# control_board.net
KiCad netlist of a schematic drawn in EAGLE
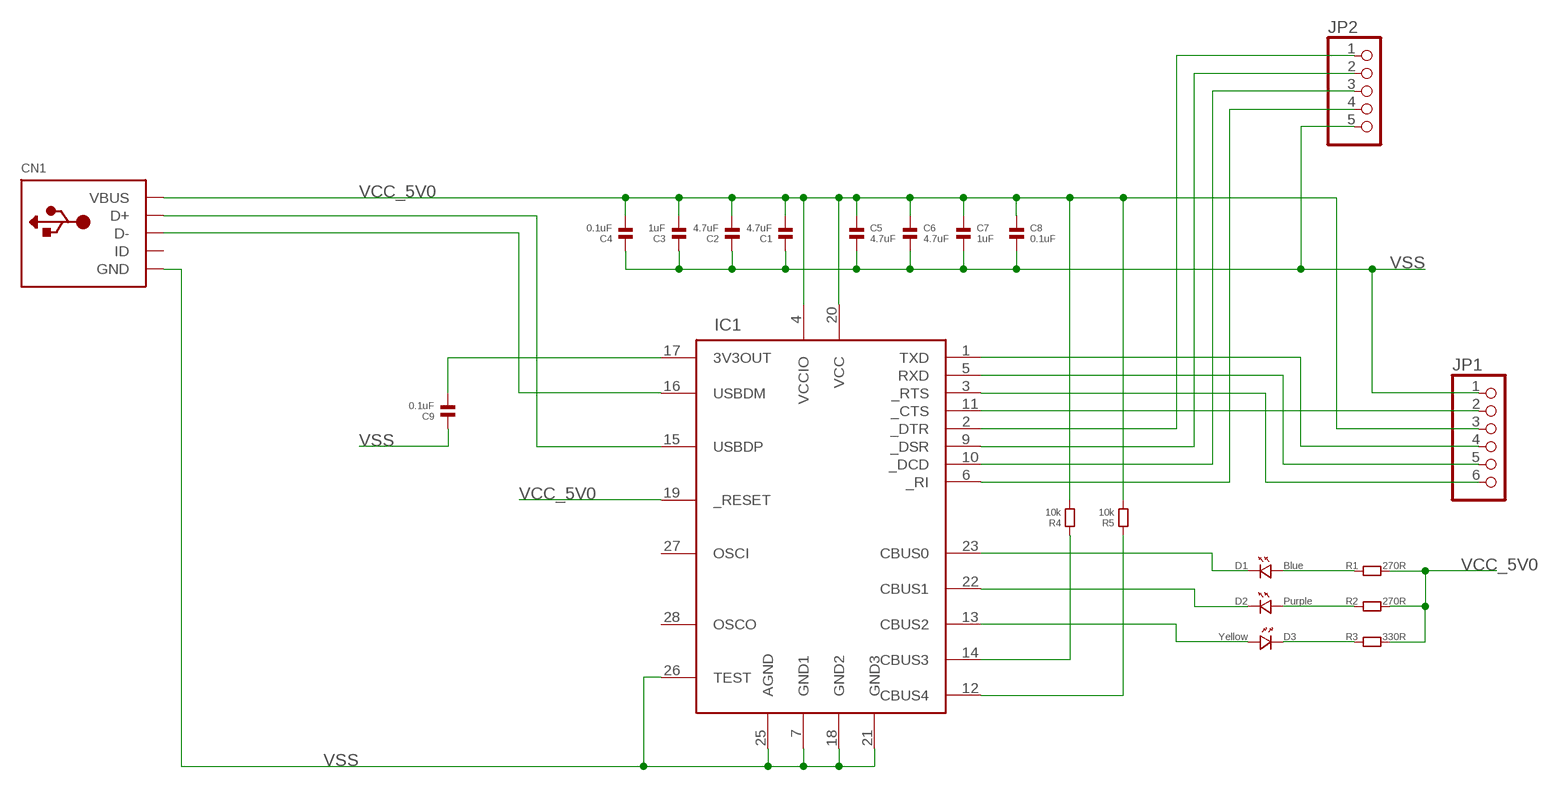
[diagram p0: schematic, sheet 1]

(export (version "E")
  (design (tool "Eeschema 10.0.6"))
  (components
    (comp (ref "C1")
      (value "4.7uF")
      (footprint "eagle-import:0603")
      (libsource (lib "eagle-import") (part "CAPACITOR.0603"))
    )
    (comp (ref "C2")
      (value "4.7uF")
      (footprint "eagle-import:0603")
      (libsource (lib "eagle-import") (part "CAPACITOR.0603"))
    )
    (comp (ref "C3")
      (value "1uF")
      (footprint "eagle-import:0603")
      (libsource (lib "eagle-import") (part "CAPACITOR.0603"))
    )
    (comp (ref "C4")
      (value "0.1uF")
      (footprint "eagle-import:0603")
      (libsource (lib "eagle-import") (part "CAPACITOR.0603"))
    )
    (comp (ref "C5")
      (value "4.7uF")
      (footprint "eagle-import:0603")
      (libsource (lib "eagle-import") (part "CAPACITOR.0603"))
    )
    (comp (ref "C6")
      (value "4.7uF")
      (footprint "eagle-import:0603")
      (libsource (lib "eagle-import") (part "CAPACITOR.0603"))
    )
    (comp (ref "C7")
      (value "1uF")
      (footprint "eagle-import:0603")
      (libsource (lib "eagle-import") (part "CAPACITOR.0603"))
    )
    (comp (ref "C8")
      (value "0.1uF")
      (footprint "eagle-import:0603")
      (libsource (lib "eagle-import") (part "CAPACITOR.0603"))
    )
    (comp (ref "C9")
      (value "0.1uF")
      (footprint "eagle-import:0603")
      (libsource (lib "eagle-import") (part "CAPACITOR.0603"))
    )
    (comp (ref "CN1")
      (value "USBMINIB")
      (footprint "eagle-import:USB-MINIB")
      (libsource (lib "eagle-import") (part "USBMINIB"))
    )
    (comp (ref "D1")
      (value "Blue")
      (footprint "eagle-import:0603.LED")
      (libsource (lib "eagle-import") (part "LED.0603"))
    )
    (comp (ref "D2")
      (value "Purple")
      (footprint "eagle-import:0603.LED")
      (libsource (lib "eagle-import") (part "LED.0603"))
    )
    (comp (ref "D3")
      (value "Yellow")
      (footprint "eagle-import:0603.LED")
      (libsource (lib "eagle-import") (part "LED.0603"))
    )
    (comp (ref "IC1")
      (value "FT232RL")
      (footprint "eagle-import:SSOP28DB")
      (libsource (lib "eagle-import") (part "FT232RL"))
    )
    (comp (ref "JP1")
      (value "PINHD-1X6")
      (footprint "eagle-import:1X06")
      (libsource (lib "eagle-import") (part "PINHD-1X6"))
    )
    (comp (ref "JP2")
      (value "PINHD-1X5")
      (footprint "eagle-import:1X05")
      (libsource (lib "eagle-import") (part "PINHD-1X5"))
    )
    (comp (ref "R1")
      (value "270R")
      (footprint "eagle-import:0603")
      (libsource (lib "eagle-import") (part "RESISTOR.0603"))
    )
    (comp (ref "R2")
      (value "270R")
      (footprint "eagle-import:0603")
      (libsource (lib "eagle-import") (part "RESISTOR.0603"))
    )
    (comp (ref "R3")
      (value "330R")
      (footprint "eagle-import:0603")
      (libsource (lib "eagle-import") (part "RESISTOR.0603"))
    )
    (comp (ref "R4")
      (value "10k")
      (footprint "eagle-import:0603")
      (libsource (lib "eagle-import") (part "RESISTOR.0603"))
    )
    (comp (ref "R5")
      (value "10k")
      (footprint "eagle-import:0603")
      (libsource (lib "eagle-import") (part "RESISTOR.0603"))
    )
  )
  (nets
    (net (code "1") (name "/VCC_5V0") (class "Default")
      (node (ref "C1") (pin "2") (pinfunction "2_2") (pintype "bidirectional"))
      (node (ref "C2") (pin "2") (pinfunction "2_2") (pintype "bidirectional"))
      (node (ref "C3") (pin "2") (pinfunction "2_2") (pintype "bidirectional"))
      (node (ref "C4") (pin "2") (pinfunction "2_2") (pintype "bidirectional"))
      (node (ref "C5") (pin "1") (pinfunction "1_1") (pintype "bidirectional"))
      (node (ref "C6") (pin "1") (pinfunction "1_1") (pintype "bidirectional"))
      (node (ref "C7") (pin "1") (pinfunction "1_1") (pintype "bidirectional"))
      (node (ref "C8") (pin "1") (pinfunction "1_1") (pintype "bidirectional"))
      (node (ref "CN1") (pin "VBUS") (pinfunction "VBUS_VBUS") (pintype "power_in"))
      (node (ref "IC1") (pin "19") (pinfunction "_RESET_19") (pintype "input"))
      (node (ref "IC1") (pin "20") (pinfunction "VCC_20") (pintype "power_in"))
      (node (ref "IC1") (pin "4") (pinfunction "VCCIO_4") (pintype "power_in"))
      (node (ref "JP1") (pin "3") (pinfunction "3_3") (pintype "passive"))
      (node (ref "R1") (pin "2") (pinfunction "2_2") (pintype "bidirectional"))
      (node (ref "R2") (pin "2") (pinfunction "2_2") (pintype "bidirectional"))
      (node (ref "R3") (pin "2") (pinfunction "2_2") (pintype "bidirectional"))
      (node (ref "R4") (pin "2") (pinfunction "2_2") (pintype "bidirectional"))
      (node (ref "R5") (pin "2") (pinfunction "2_2") (pintype "bidirectional"))
    )
    (net (code "2") (name "/VSS") (class "Default")
      (node (ref "C1") (pin "1") (pinfunction "1_1") (pintype "bidirectional"))
      (node (ref "C2") (pin "1") (pinfunction "1_1") (pintype "bidirectional"))
      (node (ref "C3") (pin "1") (pinfunction "1_1") (pintype "bidirectional"))
      (node (ref "C4") (pin "1") (pinfunction "1_1") (pintype "bidirectional"))
      (node (ref "C5") (pin "2") (pinfunction "2_2") (pintype "bidirectional"))
      (node (ref "C6") (pin "2") (pinfunction "2_2") (pintype "bidirectional"))
      (node (ref "C7") (pin "2") (pinfunction "2_2") (pintype "bidirectional"))
      (node (ref "C8") (pin "2") (pinfunction "2_2") (pintype "bidirectional"))
      (node (ref "C9") (pin "1") (pinfunction "1_1") (pintype "bidirectional"))
      (node (ref "CN1") (pin "GND") (pinfunction "GND_GND") (pintype "power_in"))
      (node (ref "IC1") (pin "18") (pinfunction "GND2_18") (pintype "power_in"))
      (node (ref "IC1") (pin "21") (pinfunction "GND3_21") (pintype "power_in"))
      (node (ref "IC1") (pin "25") (pinfunction "AGND_25") (pintype "power_in"))
      (node (ref "IC1") (pin "26") (pinfunction "TEST_26") (pintype "input"))
      (node (ref "IC1") (pin "7") (pinfunction "GND1_7") (pintype "power_in"))
      (node (ref "JP1") (pin "1") (pinfunction "1_1") (pintype "passive"))
      (node (ref "JP2") (pin "5") (pinfunction "5_5") (pintype "passive"))
    )
    (net (code "3") (name "Net-(D1-1)") (class "Default")
      (node (ref "D1") (pin "P$1") (pinfunction "1_P$1") (pintype "bidirectional"))
      (node (ref "R1") (pin "1") (pinfunction "1_1") (pintype "bidirectional"))
    )
    (net (code "4") (name "Net-(D1-2)") (class "Default")
      (node (ref "D1") (pin "P$2") (pinfunction "2_P$2") (pintype "bidirectional"))
      (node (ref "IC1") (pin "23") (pinfunction "CBUS0_23") (pintype "bidirectional"))
    )
    (net (code "5") (name "Net-(D2-1)") (class "Default")
      (node (ref "D2") (pin "P$1") (pinfunction "1_P$1") (pintype "bidirectional"))
      (node (ref "R2") (pin "1") (pinfunction "1_1") (pintype "bidirectional"))
    )
    (net (code "6") (name "Net-(D2-2)") (class "Default")
      (node (ref "D2") (pin "P$2") (pinfunction "2_P$2") (pintype "bidirectional"))
      (node (ref "IC1") (pin "22") (pinfunction "CBUS1_22") (pintype "bidirectional"))
    )
    (net (code "7") (name "Net-(D3-1)") (class "Default")
      (node (ref "D3") (pin "P$1") (pinfunction "1_P$1") (pintype "bidirectional"))
      (node (ref "IC1") (pin "13") (pinfunction "CBUS2_13") (pintype "bidirectional"))
    )
    (net (code "8") (name "Net-(D3-2)") (class "Default")
      (node (ref "D3") (pin "P$2") (pinfunction "2_P$2") (pintype "bidirectional"))
      (node (ref "R3") (pin "1") (pinfunction "1_1") (pintype "bidirectional"))
    )
    (net (code "9") (name "Net-(IC1-3V3OUT)") (class "Default")
      (node (ref "C9") (pin "2") (pinfunction "2_2") (pintype "bidirectional"))
      (node (ref "IC1") (pin "17") (pinfunction "3V3OUT_17") (pintype "output"))
    )
    (net (code "10") (name "Net-(IC1-CBUS3)") (class "Default")
      (node (ref "IC1") (pin "14") (pinfunction "CBUS3_14") (pintype "bidirectional"))
      (node (ref "R4") (pin "1") (pinfunction "1_1") (pintype "bidirectional"))
    )
    (net (code "11") (name "Net-(IC1-CBUS4)") (class "Default")
      (node (ref "IC1") (pin "12") (pinfunction "CBUS4_12") (pintype "bidirectional"))
      (node (ref "R5") (pin "1") (pinfunction "1_1") (pintype "bidirectional"))
    )
    (net (code "12") (name "Net-(IC1-RXD)") (class "Default")
      (node (ref "IC1") (pin "5") (pinfunction "RXD_5") (pintype "input"))
      (node (ref "JP1") (pin "5") (pinfunction "5_5") (pintype "passive"))
    )
    (net (code "13") (name "Net-(IC1-TXD)") (class "Default")
      (node (ref "IC1") (pin "1") (pinfunction "TXD_1") (pintype "output"))
      (node (ref "JP1") (pin "4") (pinfunction "4_4") (pintype "passive"))
    )
    (net (code "14") (name "Net-(IC1-USBDM)") (class "Default")
      (node (ref "CN1") (pin "D-") (pinfunction "D-_D-") (pintype "bidirectional"))
      (node (ref "IC1") (pin "16") (pinfunction "USBDM_16") (pintype "bidirectional"))
    )
    (net (code "15") (name "Net-(IC1-USBDP)") (class "Default")
      (node (ref "CN1") (pin "D+") (pinfunction "D+_D+") (pintype "bidirectional"))
      (node (ref "IC1") (pin "15") (pinfunction "USBDP_15") (pintype "bidirectional"))
    )
    (net (code "16") (name "Net-(IC1-_CTS)") (class "Default")
      (node (ref "IC1") (pin "11") (pinfunction "_CTS_11") (pintype "input"))
      (node (ref "JP1") (pin "2") (pinfunction "2_2") (pintype "passive"))
    )
    (net (code "17") (name "Net-(IC1-_DCD)") (class "Default")
      (node (ref "IC1") (pin "10") (pinfunction "_DCD_10") (pintype "input"))
      (node (ref "JP2") (pin "3") (pinfunction "3_3") (pintype "passive"))
    )
    (net (code "18") (name "Net-(IC1-_DSR)") (class "Default")
      (node (ref "IC1") (pin "9") (pinfunction "_DSR_9") (pintype "input"))
      (node (ref "JP2") (pin "2") (pinfunction "2_2") (pintype "passive"))
    )
    (net (code "19") (name "Net-(IC1-_DTR)") (class "Default")
      (node (ref "IC1") (pin "2") (pinfunction "_DTR_2") (pintype "output"))
      (node (ref "JP2") (pin "1") (pinfunction "1_1") (pintype "passive"))
    )
    (net (code "20") (name "Net-(IC1-_RI)") (class "Default")
      (node (ref "IC1") (pin "6") (pinfunction "_RI_6") (pintype "input"))
      (node (ref "JP2") (pin "4") (pinfunction "4_4") (pintype "passive"))
    )
    (net (code "21") (name "Net-(IC1-_RTS)") (class "Default")
      (node (ref "IC1") (pin "3") (pinfunction "_RTS_3") (pintype "output"))
      (node (ref "JP1") (pin "6") (pinfunction "6_6") (pintype "passive"))
    )
    (net (code "22") (name "unconnected-(CN1-PadID)") (class "Default")
      (node (ref "CN1") (pin "ID") (pinfunction "ID_ID") (pintype "bidirectional"))
    )
    (net (code "23") (name "unconnected-(IC1-OSCI-Pad27)") (class "Default")
      (node (ref "IC1") (pin "27") (pinfunction "OSCI_27") (pintype "input"))
    )
    (net (code "24") (name "unconnected-(IC1-OSCO-Pad28)") (class "Default")
      (node (ref "IC1") (pin "28") (pinfunction "OSCO_28") (pintype "output"))
    )
  )
)
